# Sheet1.net
KiCad netlist of a schematic drawn in Altium Designer
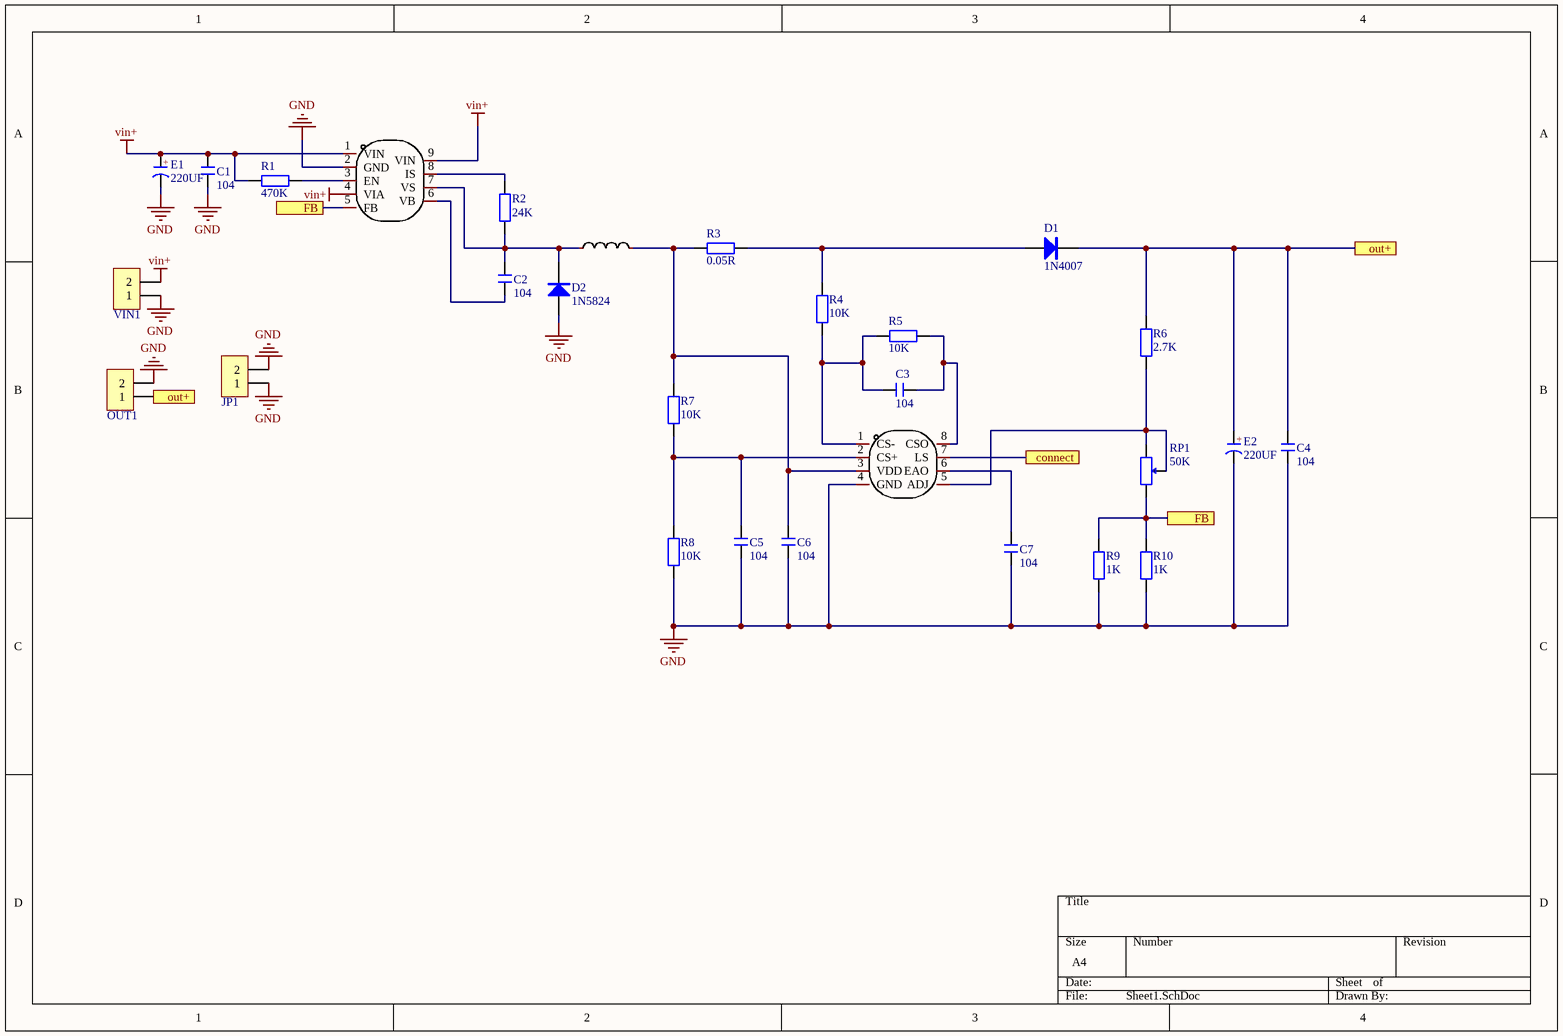
[diagram p0: Sheet1.SchDoc]

(export (version "E")
  (design (tool "Eeschema 10.0.6"))
  (components
    (comp (ref "C1")
      (value "104")
      (footprint "C 0805")
      (description "直插瓷片电容")
      (fields (field (name "版权归属") "黎明电子style"))
      (libsource (lib "1.3.2-电阻_电容_电感") (part "C-CC"))
    )
    (comp (ref "C2")
      (value "104")
      (footprint "C 0805")
      (description "直插瓷片电容")
      (fields (field (name "版权归属") "黎明电子style"))
      (libsource (lib "1.3.2-电阻_电容_电感") (part "C-CC"))
    )
    (comp (ref "C3")
      (value "104")
      (footprint "C 0805")
      (description "直插瓷片电容")
      (fields (field (name "版权归属") "黎明电子style"))
      (libsource (lib "1.3.2-电阻_电容_电感") (part "C-CC"))
    )
    (comp (ref "C4")
      (value "104")
      (footprint "C 0805")
      (description "直插瓷片电容")
      (fields (field (name "版权归属") "黎明电子style"))
      (libsource (lib "1.3.2-电阻_电容_电感") (part "C-CC"))
    )
    (comp (ref "C5")
      (value "104")
      (footprint "C 0805")
      (description "直插瓷片电容")
      (fields (field (name "版权归属") "黎明电子style"))
      (libsource (lib "1.3.2-电阻_电容_电感") (part "C-CC"))
    )
    (comp (ref "C6")
      (value "104")
      (footprint "C 0805")
      (description "直插瓷片电容")
      (fields (field (name "版权归属") "黎明电子style"))
      (libsource (lib "1.3.2-电阻_电容_电感") (part "C-CC"))
    )
    (comp (ref "C7")
      (value "104")
      (footprint "C 0805")
      (description "直插瓷片电容")
      (fields (field (name "版权归属") "黎明电子style"))
      (libsource (lib "1.3.2-电阻_电容_电感") (part "C-CC"))
    )
    (comp (ref "D1")
      (value "1N4007")
      (footprint "SMA_L4.4-W2.8-LS5.4-R-RD")
      (description "整流二极管")
      (fields (field (name "版权归属") "源创客"))
      (libsource (lib "1.3.3-二极管_整流桥") (part "1N4007"))
    )
    (comp (ref "D2")
      (value "1N5824")
      (footprint "SMA_L4.4-W2.8-LS5.4-R-RD")
      (description "整流二极管")
      (fields (field (name "版权归属") "源创客"))
      (libsource (lib "1.3.3-二极管_整流桥") (part "1N4007"))
    )
    (comp (ref "E1")
      (value "220UF")
      (footprint "CAP 3.5*8*11.5 - GD")
      (description "直插电解电容")
      (fields (field (name "版权归属") "黎明电子style"))
      (libsource (lib "1.3.2-电阻_电容_电感") (part "C-CAP"))
    )
    (comp (ref "E2")
      (value "220UF")
      (footprint "CAP 3.5*8*11.5 - GD")
      (description "直插电解电容")
      (fields (field (name "版权归属") "黎明电子style"))
      (libsource (lib "1.3.2-电阻_电容_电感") (part "C-CAP"))
    )
    (comp (ref "JP1")
      (value "HDR-1X2")
      (footprint "KF350-2P")
      (description "2P接插件")
      (fields (field (name "版权归属") "黎明电子style"))
      (libsource (lib "1.5.1-接插件") (part "Header 2"))
    )
    (comp (ref "L1")
      (value "TMPC1004H-1R0MG-D")
      (footprint "CDRH127")
      (fields (field (name "MANUFACTURER") "TAI-TECH(台庆)") (field (name "TOLERANCE") "±20%"))
      (libsource (lib "功率电感") (part "TMPC1004H-1R0MG-D"))
    )
    (comp (ref "OUT1")
      (value "HDR-1X2")
      (footprint "KF350-2P")
      (description "2P接插件")
      (fields (field (name "版权归属") "黎明电子style"))
      (libsource (lib "1.5.1-接插件") (part "Header 2"))
    )
    (comp (ref "R1")
      (value "470K")
      (footprint "R 0805")
      (description "贴片电阻")
      (fields (field (name "版权归属") "黎明电子style"))
      (libsource (lib "1.3.2-电阻_电容_电感") (part "R"))
    )
    (comp (ref "R2")
      (value "24K")
      (footprint "R 0805")
      (description "贴片电阻")
      (fields (field (name "版权归属") "黎明电子style"))
      (libsource (lib "1.3.2-电阻_电容_电感") (part "R"))
    )
    (comp (ref "R3")
      (value "0.05R")
      (footprint "R2512")
      (description "电流检测电阻")
      (fields (field (name "版权归属") "黎明电子style"))
      (libsource (lib "1.3.2-电阻_电容_电感") (part "R-I"))
    )
    (comp (ref "R4")
      (value "10K")
      (footprint "R 0805")
      (description "贴片电阻")
      (fields (field (name "版权归属") "黎明电子style"))
      (libsource (lib "1.3.2-电阻_电容_电感") (part "R"))
    )
    (comp (ref "R5")
      (value "10K")
      (footprint "R 0805")
      (description "贴片电阻")
      (fields (field (name "版权归属") "黎明电子style"))
      (libsource (lib "1.3.2-电阻_电容_电感") (part "R"))
    )
    (comp (ref "R6")
      (value "2.7K")
      (footprint "R 0805")
      (description "贴片电阻")
      (fields (field (name "版权归属") "黎明电子style"))
      (libsource (lib "1.3.2-电阻_电容_电感") (part "R"))
    )
    (comp (ref "R7")
      (value "10K")
      (footprint "R 0805")
      (description "贴片电阻")
      (fields (field (name "版权归属") "黎明电子style"))
      (libsource (lib "1.3.2-电阻_电容_电感") (part "R"))
    )
    (comp (ref "R8")
      (value "10K")
      (footprint "R 0805")
      (description "贴片电阻")
      (fields (field (name "版权归属") "黎明电子style"))
      (libsource (lib "1.3.2-电阻_电容_电感") (part "R"))
    )
    (comp (ref "R9")
      (value "1K")
      (footprint "R 0805")
      (description "贴片电阻")
      (fields (field (name "版权归属") "黎明电子style"))
      (libsource (lib "1.3.2-电阻_电容_电感") (part "R"))
    )
    (comp (ref "R10")
      (value "1K")
      (footprint "R 0805")
      (description "贴片电阻")
      (fields (field (name "版权归属") "黎明电子style"))
      (libsource (lib "1.3.2-电阻_电容_电感") (part "R"))
    )
    (comp (ref "RP1")
      (value "50K")
      (footprint "3296W")
      (description "插件单联电位器")
      (fields (field (name "版权归属") "黎明电子style"))
      (libsource (lib "1.3.2-电阻_电容_电感") (part "RP-ID"))
    )
    (comp (ref "U1")
      (value "EG1192")
      (footprint "ESOP-8_L4.9-W3.9-P1.27-LS6.0-BL-EP")
      (fields (field (name "MANUFACTURER") "EG(屹晶微)"))
      (libsource (lib "EG1192") (part "EG1192"))
    )
    (comp (ref "U2")
      (value "UCC39002D")
      (footprint "SOIC-8_L4.9-W3.9-P1.27-LS6.0-BL")
      (fields (field (name "MANUFACTURER") "TI(德州仪器)"))
      (libsource (lib "UCC39002") (part "UCC39002D"))
    )
    (comp (ref "VIN1")
      (value "HDR-1X2")
      (footprint "KF350-2P")
      (description "2P接插件")
      (fields (field (name "版权归属") "黎明电子style"))
      (libsource (lib "1.5.1-接插件") (part "Header 2"))
    )
  )
  (nets
    (net (code "1") (name "/FB") (class "Default")
      (node (ref "R10") (pin "2") (pinfunction "2_2") (pintype "passive"))
      (node (ref "R9") (pin "2") (pinfunction "2_2") (pintype "passive"))
      (node (ref "RP1") (pin "3") (pinfunction "3_3") (pintype "passive"))
      (node (ref "U1") (pin "5") (pinfunction "FB_5") (pintype "passive"))
    )
    (net (code "2") (name "/connect") (class "Default")
      (node (ref "U2") (pin "7") (pinfunction "LS_7") (pintype "passive"))
    )
    (net (code "3") (name "/out+") (class "Default")
      (node (ref "C4") (pin "2") (pinfunction "2_2") (pintype "passive"))
      (node (ref "D1") (pin "2") (pinfunction "K_2") (pintype "passive"))
      (node (ref "E2") (pin "1") (pinfunction "A_1") (pintype "passive"))
      (node (ref "OUT1") (pin "1") (pinfunction "1_1") (pintype "passive"))
      (node (ref "R6") (pin "2") (pinfunction "2_2") (pintype "passive"))
    )
    (net (code "4") (name "GND") (class "Default")
      (node (ref "C1") (pin "2") (pinfunction "2_2") (pintype "passive"))
      (node (ref "C4") (pin "1") (pinfunction "1_1") (pintype "passive"))
      (node (ref "C5") (pin "2") (pinfunction "2_2") (pintype "passive"))
      (node (ref "C6") (pin "2") (pinfunction "2_2") (pintype "passive"))
      (node (ref "C7") (pin "2") (pinfunction "2_2") (pintype "passive"))
      (node (ref "D2") (pin "1") (pinfunction "A_1") (pintype "passive"))
      (node (ref "E1") (pin "2") (pinfunction "K_2") (pintype "passive"))
      (node (ref "E2") (pin "2") (pinfunction "K_2") (pintype "passive"))
      (node (ref "JP1") (pin "1") (pinfunction "1_1") (pintype "passive"))
      (node (ref "JP1") (pin "2") (pinfunction "2_2") (pintype "passive"))
      (node (ref "OUT1") (pin "2") (pinfunction "2_2") (pintype "passive"))
      (node (ref "R10") (pin "1") (pinfunction "1_1") (pintype "passive"))
      (node (ref "R8") (pin "1") (pinfunction "1_1") (pintype "passive"))
      (node (ref "R9") (pin "1") (pinfunction "1_1") (pintype "passive"))
      (node (ref "U1") (pin "2") (pinfunction "GND_2") (pintype "passive"))
      (node (ref "U2") (pin "4") (pinfunction "GND_4") (pintype "passive"))
      (node (ref "VIN1") (pin "1") (pinfunction "1_1") (pintype "passive"))
    )
    (net (code "5") (name "Net-(D1-A)") (class "Default")
      (node (ref "D1") (pin "1") (pinfunction "A_1") (pintype "passive"))
      (node (ref "R3") (pin "2") (pinfunction "2_2") (pintype "passive"))
      (node (ref "R4") (pin "2") (pinfunction "2_2") (pintype "passive"))
    )
    (net (code "6") (name "Net-(D2-K)") (class "Default")
      (node (ref "C2") (pin "2") (pinfunction "2_2") (pintype "passive"))
      (node (ref "D2") (pin "2") (pinfunction "K_2") (pintype "passive"))
      (node (ref "L1") (pin "1") (pinfunction "1_1") (pintype "passive"))
      (node (ref "R2") (pin "1") (pinfunction "1_1") (pintype "passive"))
      (node (ref "U1") (pin "7") (pinfunction "VS_7") (pintype "passive"))
    )
    (net (code "7") (name "Net-(U1-EN)") (class "Default")
      (node (ref "R1") (pin "1") (pinfunction "1_1") (pintype "passive"))
      (node (ref "U1") (pin "3") (pinfunction "EN_3") (pintype "passive"))
    )
    (net (code "8") (name "Net-(U1-IS)") (class "Default")
      (node (ref "R2") (pin "2") (pinfunction "2_2") (pintype "passive"))
      (node (ref "U1") (pin "8") (pinfunction "IS_8") (pintype "passive"))
    )
    (net (code "9") (name "Net-(U1-VB)") (class "Default")
      (node (ref "C2") (pin "1") (pinfunction "1_1") (pintype "passive"))
      (node (ref "U1") (pin "6") (pinfunction "VB_6") (pintype "passive"))
    )
    (net (code "10") (name "Net-(U2-ADJ)") (class "Default")
      (node (ref "R6") (pin "1") (pinfunction "1_1") (pintype "passive"))
      (node (ref "RP1") (pin "1") (pinfunction "1_1") (pintype "passive"))
      (node (ref "RP1") (pin "2") (pinfunction "2_2") (pintype "passive"))
      (node (ref "U2") (pin "5") (pinfunction "ADJ_5") (pintype "passive"))
    )
    (net (code "11") (name "Net-(U2-CS+)") (class "Default")
      (node (ref "C5") (pin "1") (pinfunction "1_1") (pintype "passive"))
      (node (ref "R7") (pin "1") (pinfunction "1_1") (pintype "passive"))
      (node (ref "R8") (pin "2") (pinfunction "2_2") (pintype "passive"))
      (node (ref "U2") (pin "2") (pinfunction "CS+_2") (pintype "passive"))
    )
    (net (code "12") (name "Net-(U2-CS-)") (class "Default")
      (node (ref "C3") (pin "2") (pinfunction "2_2") (pintype "passive"))
      (node (ref "R4") (pin "1") (pinfunction "1_1") (pintype "passive"))
      (node (ref "R5") (pin "2") (pinfunction "2_2") (pintype "passive"))
      (node (ref "U2") (pin "1") (pinfunction "CS-_1") (pintype "passive"))
    )
    (net (code "13") (name "Net-(U2-CSO)") (class "Default")
      (node (ref "C3") (pin "1") (pinfunction "1_1") (pintype "passive"))
      (node (ref "R5") (pin "1") (pinfunction "1_1") (pintype "passive"))
      (node (ref "U2") (pin "8") (pinfunction "CSO_8") (pintype "passive"))
    )
    (net (code "14") (name "Net-(U2-EAO)") (class "Default")
      (node (ref "C7") (pin "1") (pinfunction "1_1") (pintype "passive"))
      (node (ref "U2") (pin "6") (pinfunction "EAO_6") (pintype "passive"))
    )
    (net (code "15") (name "Net-(U2-VDD)") (class "Default")
      (node (ref "C6") (pin "1") (pinfunction "1_1") (pintype "passive"))
      (node (ref "L1") (pin "2") (pinfunction "2_2") (pintype "passive"))
      (node (ref "R3") (pin "1") (pinfunction "1_1") (pintype "passive"))
      (node (ref "R7") (pin "2") (pinfunction "2_2") (pintype "passive"))
      (node (ref "U2") (pin "3") (pinfunction "VDD_3") (pintype "passive"))
    )
    (net (code "16") (name "vin+") (class "Default")
      (node (ref "C1") (pin "1") (pinfunction "1_1") (pintype "passive"))
      (node (ref "E1") (pin "1") (pinfunction "A_1") (pintype "passive"))
      (node (ref "R1") (pin "2") (pinfunction "2_2") (pintype "passive"))
      (node (ref "U1") (pin "1") (pinfunction "VIN_1") (pintype "passive"))
      (node (ref "U1") (pin "4") (pinfunction "VIA_4") (pintype "passive"))
      (node (ref "U1") (pin "9") (pinfunction "VIN_9") (pintype "passive"))
      (node (ref "VIN1") (pin "2") (pinfunction "2_2") (pintype "passive"))
    )
  )
)
